# Sheet1.net
KiCad netlist of a schematic drawn in Altium Designer
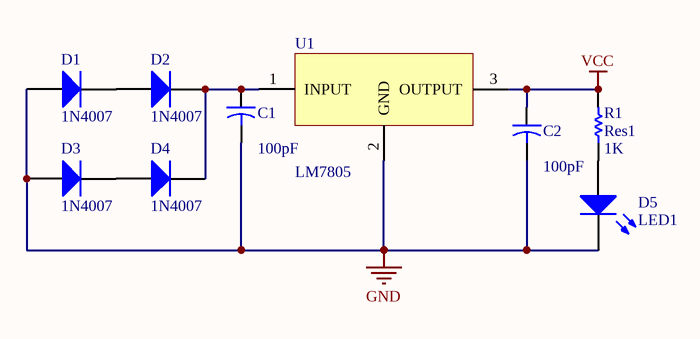
[diagram p0: Sheet1.SchDoc]

(export (version "E")
  (design (tool "Eeschema 10.0.6"))
  (components
    (comp (ref "C1")
      (value "100pF")
      (footprint "CAPR5-4X5")
      (description "Capacitor")
      (fields (field (name "Comment") "Cap2") (field (name "PUBLISHER") "Altium Limited"))
      (libsource (lib "Miscellaneous Devices") (part "Cap2"))
    )
    (comp (ref "C2")
      (value "100pF")
      (footprint "CAPR5-4X5")
      (description "Capacitor")
      (fields (field (name "Comment") "Cap2") (field (name "PUBLISHER") "Altium Limited"))
      (libsource (lib "Miscellaneous Devices") (part "Cap2"))
    )
    (comp (ref "D1")
      (value "1N4007")
      (footprint "DO-41")
      (description "1 Amp General Purpose Rectifier")
      (fields (field (name "PUBLISHER") "Altium Limited"))
      (libsource (lib "Miscellaneous Devices") (part "Diode 1N4007"))
    )
    (comp (ref "D2")
      (value "1N4007")
      (footprint "DO-41")
      (description "1 Amp General Purpose Rectifier")
      (fields (field (name "PUBLISHER") "Altium Limited"))
      (libsource (lib "Miscellaneous Devices") (part "Diode 1N4007"))
    )
    (comp (ref "D3")
      (value "1N4007")
      (footprint "DO-41")
      (description "1 Amp General Purpose Rectifier")
      (fields (field (name "PUBLISHER") "Altium Limited"))
      (libsource (lib "Miscellaneous Devices") (part "Diode 1N4007"))
    )
    (comp (ref "D4")
      (value "1N4007")
      (footprint "DO-41")
      (description "1 Amp General Purpose Rectifier")
      (fields (field (name "PUBLISHER") "Altium Limited"))
      (libsource (lib "Miscellaneous Devices") (part "Diode 1N4007"))
    )
    (comp (ref "D5")
      (value "LED1")
      (footprint "LED-1")
      (description "Typical RED GaAs LED")
      (fields (field (name "PUBLISHER") "Altium Limited"))
      (libsource (lib "Miscellaneous Devices") (part "LED1"))
    )
    (comp (ref "R1")
      (value "Res1")
      (footprint "AXIAL-0.3")
      (description "Resistor")
      (fields (field (name "ALTIUM_VALUE") "1K") (field (name "PUBLISHER") "Altium Limited"))
      (libsource (lib "Miscellaneous Devices") (part "Res1"))
    )
    (comp (ref "U1") (value "LM7805") (footprint "LM7805") (libsource (lib "LM7805") (part "Component_1")))
  )
  (nets
    (net (code "1") (name "GND") (class "Default")
      (node (ref "C1") (pin "2") (pinfunction "2_2") (pintype "passive"))
      (node (ref "C2") (pin "2") (pinfunction "2_2") (pintype "passive"))
      (node (ref "D1") (pin "1") (pinfunction "A_1") (pintype "passive"))
      (node (ref "D3") (pin "1") (pinfunction "A_1") (pintype "passive"))
      (node (ref "D5") (pin "2") (pinfunction "K_2") (pintype "passive"))
      (node (ref "U1") (pin "2") (pinfunction "GND_2") (pintype "passive"))
    )
    (net (code "2") (name "Net-(D1-K)") (class "Default")
      (node (ref "D1") (pin "2") (pinfunction "K_2") (pintype "passive"))
      (node (ref "D2") (pin "1") (pinfunction "A_1") (pintype "passive"))
    )
    (net (code "3") (name "Net-(D2-K)") (class "Default")
      (node (ref "C1") (pin "1") (pinfunction "1_1") (pintype "passive"))
      (node (ref "D2") (pin "2") (pinfunction "K_2") (pintype "passive"))
      (node (ref "D4") (pin "2") (pinfunction "K_2") (pintype "passive"))
      (node (ref "U1") (pin "1") (pinfunction "INPUT_1") (pintype "passive"))
    )
    (net (code "4") (name "Net-(D3-K)") (class "Default")
      (node (ref "D3") (pin "2") (pinfunction "K_2") (pintype "passive"))
      (node (ref "D4") (pin "1") (pinfunction "A_1") (pintype "passive"))
    )
    (net (code "5") (name "Net-(D5-A)") (class "Default")
      (node (ref "D5") (pin "1") (pinfunction "A_1") (pintype "passive"))
      (node (ref "R1") (pin "1") (pinfunction "1_1") (pintype "passive"))
    )
    (net (code "6") (name "VCC") (class "Default")
      (node (ref "C2") (pin "1") (pinfunction "1_1") (pintype "passive"))
      (node (ref "R1") (pin "2") (pinfunction "2_2") (pintype "passive"))
      (node (ref "U1") (pin "3") (pinfunction "OUTPUT_3") (pintype "passive"))
    )
  )
)
